# coyote_1.net
KiCad netlist of a schematic drawn in EAGLE
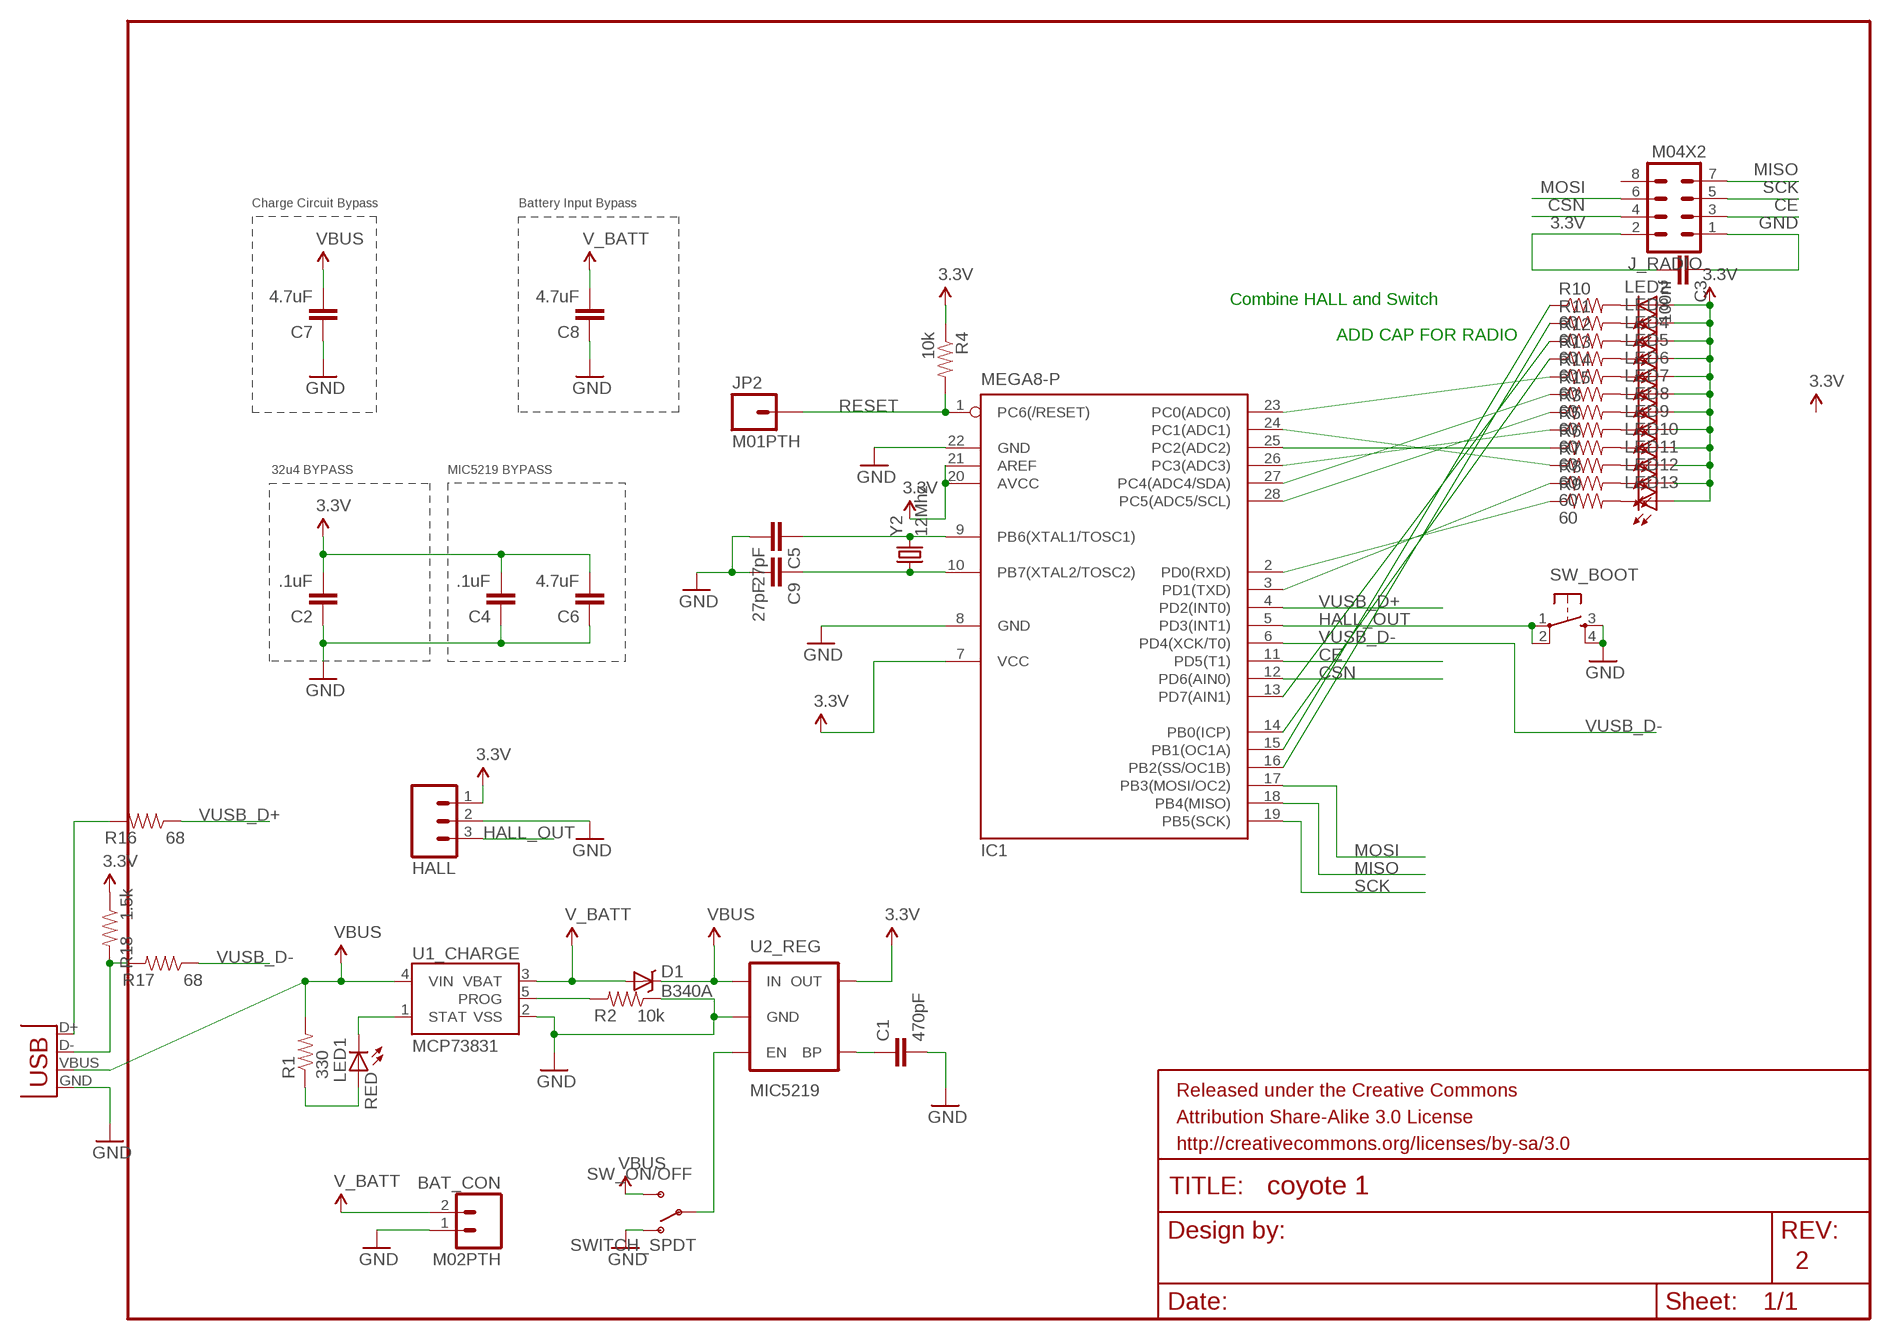
[diagram p0: schematic, sheet 1]

(export (version "E")
  (design (tool "Eeschema 10.0.6"))
  (components
    (comp (ref "BAT_CON")
      (value "M02PTH")
      (footprint "eagle-import:1X02")
      (libsource (lib "eagle-import") (part "M02PTH"))
    )
    (comp (ref "C1")
      (value "470pF")
      (footprint "eagle-import:1206")
      (libsource (lib "eagle-import") (part "CAP1206"))
    )
    (comp (ref "C2")
      (value ".1uF")
      (footprint "eagle-import:1206")
      (libsource (lib "eagle-import") (part "CAP1206"))
    )
    (comp (ref "C3")
      (value "100nf")
      (footprint "eagle-import:1206")
      (libsource (lib "eagle-import") (part "CAP1206"))
    )
    (comp (ref "C4")
      (value ".1uF")
      (footprint "eagle-import:1206")
      (libsource (lib "eagle-import") (part "CAP1206"))
    )
    (comp (ref "C5")
      (value "27pF")
      (footprint "eagle-import:1206")
      (libsource (lib "eagle-import") (part "CAP1206"))
    )
    (comp (ref "C6")
      (value "4.7uF")
      (footprint "eagle-import:1206")
      (libsource (lib "eagle-import") (part "CAP1206"))
    )
    (comp (ref "C7")
      (value "4.7uF")
      (footprint "eagle-import:1206")
      (libsource (lib "eagle-import") (part "CAP1206"))
    )
    (comp (ref "C8")
      (value "4.7uF")
      (footprint "eagle-import:1206")
      (libsource (lib "eagle-import") (part "CAP1206"))
    )
    (comp (ref "C9")
      (value "27pF")
      (footprint "eagle-import:1206")
      (libsource (lib "eagle-import") (part "CAP1206"))
    )
    (comp (ref "D1")
      (value "B340A")
      (footprint "eagle-import:SMA-DIODE")
      (libsource (lib "eagle-import") (part "DIODE-SCHOTTKY_"))
    )
    (comp (ref "HALL")
      (value "M03PTH")
      (footprint "eagle-import:1X03")
      (libsource (lib "eagle-import") (part "M03PTH"))
    )
    (comp (ref "IC1")
      (value "MEGA8-P")
      (footprint "eagle-import:DIL28-3")
      (libsource (lib "eagle-import") (part "MEGA8-P"))
    )
    (comp (ref "JP1")
      (value "USB-MB-H")
      (footprint "eagle-import:USB-MB-H")
      (libsource (lib "eagle-import") (part "USB-MB-H"))
    )
    (comp (ref "JP2")
      (value "M01PTH")
      (footprint "eagle-import:1X01")
      (libsource (lib "eagle-import") (part "M01PTH"))
    )
    (comp (ref "J_RADIO")
      (value "M04X2")
      (footprint "eagle-import:2X4")
      (libsource (lib "eagle-import") (part "M04X2"))
    )
    (comp (ref "LED1")
      (value "RED")
      (footprint "eagle-import:LED-1206")
      (libsource (lib "eagle-import") (part "LED1206"))
    )
    (comp (ref "LED2")
      (value "LED1206")
      (footprint "eagle-import:LED-1206")
      (libsource (lib "eagle-import") (part "LED1206"))
    )
    (comp (ref "LED3")
      (value "LED1206")
      (footprint "eagle-import:LED-1206")
      (libsource (lib "eagle-import") (part "LED1206"))
    )
    (comp (ref "LED4")
      (value "LED1206")
      (footprint "eagle-import:LED-1206")
      (libsource (lib "eagle-import") (part "LED1206"))
    )
    (comp (ref "LED5")
      (value "LED1206")
      (footprint "eagle-import:LED-1206")
      (libsource (lib "eagle-import") (part "LED1206"))
    )
    (comp (ref "LED6")
      (value "LED1206")
      (footprint "eagle-import:LED-1206")
      (libsource (lib "eagle-import") (part "LED1206"))
    )
    (comp (ref "LED7")
      (value "LED1206")
      (footprint "eagle-import:LED-1206")
      (libsource (lib "eagle-import") (part "LED1206"))
    )
    (comp (ref "LED8")
      (value "LED1206")
      (footprint "eagle-import:LED-1206")
      (libsource (lib "eagle-import") (part "LED1206"))
    )
    (comp (ref "LED9")
      (value "LED1206")
      (footprint "eagle-import:LED-1206")
      (libsource (lib "eagle-import") (part "LED1206"))
    )
    (comp (ref "LED10")
      (value "LED1206")
      (footprint "eagle-import:LED-1206")
      (libsource (lib "eagle-import") (part "LED1206"))
    )
    (comp (ref "LED11")
      (value "LED1206")
      (footprint "eagle-import:LED-1206")
      (libsource (lib "eagle-import") (part "LED1206"))
    )
    (comp (ref "LED12")
      (value "LED1206")
      (footprint "eagle-import:LED-1206")
      (libsource (lib "eagle-import") (part "LED1206"))
    )
    (comp (ref "LED13")
      (value "LED1206")
      (footprint "eagle-import:LED-1206")
      (libsource (lib "eagle-import") (part "LED1206"))
    )
    (comp (ref "R1")
      (value "330")
      (footprint "eagle-import:1206")
      (libsource (lib "eagle-import") (part "RESISTOR1206"))
    )
    (comp (ref "R2")
      (value "10k")
      (footprint "eagle-import:1206")
      (libsource (lib "eagle-import") (part "RESISTOR1206"))
    )
    (comp (ref "R3")
      (value "60")
      (footprint "eagle-import:1206")
      (libsource (lib "eagle-import") (part "RESISTOR1206"))
    )
    (comp (ref "R4")
      (value "10k")
      (footprint "eagle-import:1206")
      (libsource (lib "eagle-import") (part "RESISTOR1206"))
    )
    (comp (ref "R5")
      (value "60")
      (footprint "eagle-import:1206")
      (libsource (lib "eagle-import") (part "RESISTOR1206"))
    )
    (comp (ref "R6")
      (value "60")
      (footprint "eagle-import:1206")
      (libsource (lib "eagle-import") (part "RESISTOR1206"))
    )
    (comp (ref "R7")
      (value "60")
      (footprint "eagle-import:1206")
      (libsource (lib "eagle-import") (part "RESISTOR1206"))
    )
    (comp (ref "R8")
      (value "60")
      (footprint "eagle-import:1206")
      (libsource (lib "eagle-import") (part "RESISTOR1206"))
    )
    (comp (ref "R9")
      (value "60")
      (footprint "eagle-import:1206")
      (libsource (lib "eagle-import") (part "RESISTOR1206"))
    )
    (comp (ref "R10")
      (value "60")
      (footprint "eagle-import:1206")
      (libsource (lib "eagle-import") (part "RESISTOR1206"))
    )
    (comp (ref "R11")
      (value "60")
      (footprint "eagle-import:1206")
      (libsource (lib "eagle-import") (part "RESISTOR1206"))
    )
    (comp (ref "R12")
      (value "60")
      (footprint "eagle-import:1206")
      (libsource (lib "eagle-import") (part "RESISTOR1206"))
    )
    (comp (ref "R13")
      (value "60")
      (footprint "eagle-import:1206")
      (libsource (lib "eagle-import") (part "RESISTOR1206"))
    )
    (comp (ref "R14")
      (value "60")
      (footprint "eagle-import:1206")
      (libsource (lib "eagle-import") (part "RESISTOR1206"))
    )
    (comp (ref "R15")
      (value "60")
      (footprint "eagle-import:1206")
      (libsource (lib "eagle-import") (part "RESISTOR1206"))
    )
    (comp (ref "R16")
      (value "68")
      (footprint "eagle-import:1206")
      (libsource (lib "eagle-import") (part "RESISTOR1206"))
    )
    (comp (ref "R17")
      (value "68")
      (footprint "eagle-import:1206")
      (libsource (lib "eagle-import") (part "RESISTOR1206"))
    )
    (comp (ref "R18")
      (value "1.5k")
      (footprint "eagle-import:1206")
      (libsource (lib "eagle-import") (part "RESISTOR1206"))
    )
    (comp (ref "SW_BOOT")
      (value "TAC_SWITCHPTH")
      (footprint "eagle-import:TACTILE-PTH")
      (libsource (lib "eagle-import") (part "TAC_SWITCHPTH"))
    )
    (comp (ref "SW_ON/OFF")
      (value "SWITCH_SPDT")
      (footprint "eagle-import:KPS-1290")
      (libsource (lib "eagle-import") (part "SWITCH_SPDT"))
    )
    (comp (ref "U1_CHARGE")
      (value "MCP73831")
      (footprint "eagle-import:SOT23-5")
      (libsource (lib "eagle-import") (part "MCP73831"))
    )
    (comp (ref "U2_REG")
      (value "MIC5219")
      (footprint "eagle-import:SOT23-5")
      (libsource (lib "eagle-import") (part "V_REG_MIC5219SMD"))
    )
    (comp (ref "Y2")
      (value "12Mhz")
      (footprint "eagle-import:HC49US")
      (libsource (lib "eagle-import") (part "CRYSTALHC49US"))
    )
  )
  (nets
    (net (code "1") (name "/CE") (class "Default")
      (node (ref "IC1") (pin "11") (pinfunction "PD5(T1)_11") (pintype "bidirectional"))
      (node (ref "J_RADIO") (pin "3") (pinfunction "3_3") (pintype "passive"))
    )
    (net (code "2") (name "/CSN") (class "Default")
      (node (ref "IC1") (pin "12") (pinfunction "PD6(AIN0)_12") (pintype "bidirectional"))
      (node (ref "J_RADIO") (pin "4") (pinfunction "4_4") (pintype "passive"))
    )
    (net (code "3") (name "/HALL_OUT") (class "Default")
      (node (ref "HALL") (pin "3") (pinfunction "3_3") (pintype "passive"))
      (node (ref "IC1") (pin "5") (pinfunction "PD3(INT1)_5") (pintype "bidirectional"))
      (node (ref "SW_BOOT") (pin "1") (pinfunction "1_1") (pintype "passive"))
      (node (ref "SW_BOOT") (pin "2") (pinfunction "2_2") (pintype "passive"))
    )
    (net (code "4") (name "/MISO") (class "Default")
      (node (ref "IC1") (pin "18") (pinfunction "PB4(MISO)_18") (pintype "bidirectional"))
      (node (ref "J_RADIO") (pin "7") (pinfunction "7_7") (pintype "passive"))
    )
    (net (code "5") (name "/MOSI") (class "Default")
      (node (ref "IC1") (pin "17") (pinfunction "PB3(MOSI/OC2)_17") (pintype "bidirectional"))
      (node (ref "J_RADIO") (pin "6") (pinfunction "6_6") (pintype "passive"))
    )
    (net (code "6") (name "/RESET") (class "Default")
      (node (ref "IC1") (pin "1") (pinfunction "PC6(/RESET)_1") (pintype "bidirectional"))
      (node (ref "JP2") (pin "1") (pinfunction "1_1") (pintype "passive"))
      (node (ref "R4") (pin "2") (pinfunction "2_2") (pintype "passive"))
    )
    (net (code "7") (name "/SCK") (class "Default")
      (node (ref "IC1") (pin "19") (pinfunction "PB5(SCK)_19") (pintype "bidirectional"))
      (node (ref "J_RADIO") (pin "5") (pinfunction "5_5") (pintype "passive"))
    )
    (net (code "8") (name "/VUSB_D+") (class "Default")
      (node (ref "IC1") (pin "4") (pinfunction "PD2(INT0)_4") (pintype "bidirectional"))
      (node (ref "R16") (pin "1") (pinfunction "1_1") (pintype "passive"))
    )
    (net (code "9") (name "/VUSB_D-") (class "Default")
      (node (ref "IC1") (pin "6") (pinfunction "PD4(XCK/T0)_6") (pintype "bidirectional"))
      (node (ref "R17") (pin "1") (pinfunction "1_1") (pintype "passive"))
    )
    (net (code "10") (name "3.3V") (class "Default")
      (node (ref "C2") (pin "2") (pinfunction "2_2") (pintype "passive"))
      (node (ref "C3") (pin "2") (pinfunction "2_2") (pintype "passive"))
      (node (ref "C4") (pin "2") (pinfunction "2_2") (pintype "passive"))
      (node (ref "C6") (pin "2") (pinfunction "2_2") (pintype "passive"))
      (node (ref "HALL") (pin "1") (pinfunction "1_1") (pintype "passive"))
      (node (ref "IC1") (pin "20") (pinfunction "AVCC_20") (pintype "power_in"))
      (node (ref "IC1") (pin "21") (pinfunction "AREF_21") (pintype "passive"))
      (node (ref "IC1") (pin "7") (pinfunction "VCC_7") (pintype "power_in"))
      (node (ref "J_RADIO") (pin "2") (pinfunction "2_2") (pintype "passive"))
      (node (ref "LED10") (pin "A") (pinfunction "A_A") (pintype "passive"))
      (node (ref "LED11") (pin "A") (pinfunction "A_A") (pintype "passive"))
      (node (ref "LED12") (pin "A") (pinfunction "A_A") (pintype "passive"))
      (node (ref "LED13") (pin "A") (pinfunction "A_A") (pintype "passive"))
      (node (ref "LED2") (pin "A") (pinfunction "A_A") (pintype "passive"))
      (node (ref "LED3") (pin "A") (pinfunction "A_A") (pintype "passive"))
      (node (ref "LED4") (pin "A") (pinfunction "A_A") (pintype "passive"))
      (node (ref "LED5") (pin "A") (pinfunction "A_A") (pintype "passive"))
      (node (ref "LED6") (pin "A") (pinfunction "A_A") (pintype "passive"))
      (node (ref "LED7") (pin "A") (pinfunction "A_A") (pintype "passive"))
      (node (ref "LED8") (pin "A") (pinfunction "A_A") (pintype "passive"))
      (node (ref "LED9") (pin "A") (pinfunction "A_A") (pintype "passive"))
      (node (ref "R18") (pin "1") (pinfunction "1_1") (pintype "passive"))
      (node (ref "R4") (pin "1") (pinfunction "1_1") (pintype "passive"))
      (node (ref "U2_REG") (pin "5") (pinfunction "OUT_5") (pintype "passive"))
    )
    (net (code "11") (name "GND") (class "Default")
      (node (ref "BAT_CON") (pin "1") (pinfunction "1_1") (pintype "passive"))
      (node (ref "C1") (pin "2") (pinfunction "2_2") (pintype "passive"))
      (node (ref "C2") (pin "1") (pinfunction "1_1") (pintype "passive"))
      (node (ref "C3") (pin "1") (pinfunction "1_1") (pintype "passive"))
      (node (ref "C4") (pin "1") (pinfunction "1_1") (pintype "passive"))
      (node (ref "C5") (pin "2") (pinfunction "2_2") (pintype "passive"))
      (node (ref "C6") (pin "1") (pinfunction "1_1") (pintype "passive"))
      (node (ref "C7") (pin "1") (pinfunction "1_1") (pintype "passive"))
      (node (ref "C8") (pin "1") (pinfunction "1_1") (pintype "passive"))
      (node (ref "C9") (pin "2") (pinfunction "2_2") (pintype "passive"))
      (node (ref "HALL") (pin "2") (pinfunction "2_2") (pintype "passive"))
      (node (ref "IC1") (pin "22") (pinfunction "GND_22") (pintype "power_in"))
      (node (ref "IC1") (pin "8") (pinfunction "GND_8") (pintype "power_in"))
      (node (ref "JP1") (pin "GND") (pinfunction "GND_GND") (pintype "bidirectional"))
      (node (ref "J_RADIO") (pin "1") (pinfunction "1_1") (pintype "passive"))
      (node (ref "R2") (pin "1") (pinfunction "1_1") (pintype "passive"))
      (node (ref "SW_BOOT") (pin "3") (pinfunction "3_3") (pintype "passive"))
      (node (ref "SW_BOOT") (pin "4") (pinfunction "4_4") (pintype "passive"))
      (node (ref "SW_ON/OFF") (pin "O") (pinfunction "O_O") (pintype "passive"))
      (node (ref "U1_CHARGE") (pin "2") (pinfunction "VSS_2") (pintype "power_in"))
      (node (ref "U2_REG") (pin "2") (pinfunction "GND_2") (pintype "input"))
    )
    (net (code "12") (name "Net-(IC1-PB0(ICP))") (class "Default")
      (node (ref "IC1") (pin "14") (pinfunction "PB0(ICP)_14") (pintype "bidirectional"))
      (node (ref "R13") (pin "1") (pinfunction "1_1") (pintype "passive"))
    )
    (net (code "13") (name "Net-(IC1-PB1(OC1A))") (class "Default")
      (node (ref "IC1") (pin "15") (pinfunction "PB1(OC1A)_15") (pintype "bidirectional"))
      (node (ref "R10") (pin "1") (pinfunction "1_1") (pintype "passive"))
    )
    (net (code "14") (name "Net-(IC1-PB2(SS{slash}OC1B))") (class "Default")
      (node (ref "IC1") (pin "16") (pinfunction "PB2(SS/OC1B)_16") (pintype "bidirectional"))
      (node (ref "R11") (pin "1") (pinfunction "1_1") (pintype "passive"))
    )
    (net (code "15") (name "Net-(IC1-PB6(XTAL1{slash}TOSC1))") (class "Default")
      (node (ref "C5") (pin "1") (pinfunction "1_1") (pintype "passive"))
      (node (ref "IC1") (pin "9") (pinfunction "PB6(XTAL1/TOSC1)_9") (pintype "bidirectional"))
      (node (ref "Y2") (pin "2") (pinfunction "2_2") (pintype "passive"))
    )
    (net (code "16") (name "Net-(IC1-PB7(XTAL2{slash}TOSC2))") (class "Default")
      (node (ref "C9") (pin "1") (pinfunction "1_1") (pintype "passive"))
      (node (ref "IC1") (pin "10") (pinfunction "PB7(XTAL2/TOSC2)_10") (pintype "bidirectional"))
      (node (ref "Y2") (pin "1") (pinfunction "1_1") (pintype "passive"))
    )
    (net (code "17") (name "Net-(IC1-PC0(ADC0))") (class "Default")
      (node (ref "IC1") (pin "23") (pinfunction "PC0(ADC0)_23") (pintype "bidirectional"))
      (node (ref "R14") (pin "1") (pinfunction "1_1") (pintype "passive"))
    )
    (net (code "18") (name "Net-(IC1-PC1(ADC1))") (class "Default")
      (node (ref "IC1") (pin "24") (pinfunction "PC1(ADC1)_24") (pintype "bidirectional"))
      (node (ref "R7") (pin "1") (pinfunction "1_1") (pintype "passive"))
    )
    (net (code "19") (name "Net-(IC1-PC2(ADC2))") (class "Default")
      (node (ref "IC1") (pin "25") (pinfunction "PC2(ADC2)_25") (pintype "bidirectional"))
      (node (ref "R6") (pin "1") (pinfunction "1_1") (pintype "passive"))
    )
    (net (code "20") (name "Net-(IC1-PC3(ADC3))") (class "Default")
      (node (ref "IC1") (pin "26") (pinfunction "PC3(ADC3)_26") (pintype "bidirectional"))
      (node (ref "R5") (pin "1") (pinfunction "1_1") (pintype "passive"))
    )
    (net (code "21") (name "Net-(IC1-PC4(ADC4{slash}SDA))") (class "Default")
      (node (ref "IC1") (pin "27") (pinfunction "PC4(ADC4/SDA)_27") (pintype "bidirectional"))
      (node (ref "R15") (pin "1") (pinfunction "1_1") (pintype "passive"))
    )
    (net (code "22") (name "Net-(IC1-PC5(ADC5{slash}SCL))") (class "Default")
      (node (ref "IC1") (pin "28") (pinfunction "PC5(ADC5/SCL)_28") (pintype "bidirectional"))
      (node (ref "R3") (pin "1") (pinfunction "1_1") (pintype "passive"))
    )
    (net (code "23") (name "Net-(IC1-PD0(RXD))") (class "Default")
      (node (ref "IC1") (pin "2") (pinfunction "PD0(RXD)_2") (pintype "bidirectional"))
      (node (ref "R9") (pin "1") (pinfunction "1_1") (pintype "passive"))
    )
    (net (code "24") (name "Net-(IC1-PD1(TXD))") (class "Default")
      (node (ref "IC1") (pin "3") (pinfunction "PD1(TXD)_3") (pintype "bidirectional"))
      (node (ref "R8") (pin "1") (pinfunction "1_1") (pintype "passive"))
    )
    (net (code "25") (name "Net-(IC1-PD7(AIN1))") (class "Default")
      (node (ref "IC1") (pin "13") (pinfunction "PD7(AIN1)_13") (pintype "bidirectional"))
      (node (ref "R12") (pin "1") (pinfunction "1_1") (pintype "passive"))
    )
    (net (code "26") (name "Net-(JP1-PadD+)") (class "Default")
      (node (ref "JP1") (pin "D+") (pinfunction "D+_D+") (pintype "bidirectional"))
      (node (ref "R16") (pin "2") (pinfunction "2_2") (pintype "passive"))
    )
    (net (code "27") (name "Net-(JP1-PadD-)") (class "Default")
      (node (ref "JP1") (pin "D-") (pinfunction "D-_D-") (pintype "bidirectional"))
      (node (ref "R17") (pin "2") (pinfunction "2_2") (pintype "passive"))
      (node (ref "R18") (pin "2") (pinfunction "2_2") (pintype "passive"))
    )
    (net (code "28") (name "Net-(LED1-PadA)") (class "Default")
      (node (ref "LED1") (pin "A") (pinfunction "A_A") (pintype "passive"))
      (node (ref "R1") (pin "1") (pinfunction "1_1") (pintype "passive"))
    )
    (net (code "29") (name "Net-(LED2-PadC)") (class "Default")
      (node (ref "LED2") (pin "C") (pinfunction "C_C") (pintype "passive"))
      (node (ref "R10") (pin "2") (pinfunction "2_2") (pintype "passive"))
    )
    (net (code "30") (name "Net-(LED3-PadC)") (class "Default")
      (node (ref "LED3") (pin "C") (pinfunction "C_C") (pintype "passive"))
      (node (ref "R11") (pin "2") (pinfunction "2_2") (pintype "passive"))
    )
    (net (code "31") (name "Net-(LED4-PadC)") (class "Default")
      (node (ref "LED4") (pin "C") (pinfunction "C_C") (pintype "passive"))
      (node (ref "R12") (pin "2") (pinfunction "2_2") (pintype "passive"))
    )
    (net (code "32") (name "Net-(LED5-PadC)") (class "Default")
      (node (ref "LED5") (pin "C") (pinfunction "C_C") (pintype "passive"))
      (node (ref "R13") (pin "2") (pinfunction "2_2") (pintype "passive"))
    )
    (net (code "33") (name "Net-(LED6-PadC)") (class "Default")
      (node (ref "LED6") (pin "C") (pinfunction "C_C") (pintype "passive"))
      (node (ref "R14") (pin "2") (pinfunction "2_2") (pintype "passive"))
    )
    (net (code "34") (name "Net-(LED7-PadC)") (class "Default")
      (node (ref "LED7") (pin "C") (pinfunction "C_C") (pintype "passive"))
      (node (ref "R15") (pin "2") (pinfunction "2_2") (pintype "passive"))
    )
    (net (code "35") (name "Net-(LED8-PadC)") (class "Default")
      (node (ref "LED8") (pin "C") (pinfunction "C_C") (pintype "passive"))
      (node (ref "R3") (pin "2") (pinfunction "2_2") (pintype "passive"))
    )
    (net (code "36") (name "Net-(LED9-PadC)") (class "Default")
      (node (ref "LED9") (pin "C") (pinfunction "C_C") (pintype "passive"))
      (node (ref "R5") (pin "2") (pinfunction "2_2") (pintype "passive"))
    )
    (net (code "37") (name "Net-(LED10-PadC)") (class "Default")
      (node (ref "LED10") (pin "C") (pinfunction "C_C") (pintype "passive"))
      (node (ref "R6") (pin "2") (pinfunction "2_2") (pintype "passive"))
    )
    (net (code "38") (name "Net-(LED11-PadC)") (class "Default")
      (node (ref "LED11") (pin "C") (pinfunction "C_C") (pintype "passive"))
      (node (ref "R7") (pin "2") (pinfunction "2_2") (pintype "passive"))
    )
    (net (code "39") (name "Net-(LED12-PadC)") (class "Default")
      (node (ref "LED12") (pin "C") (pinfunction "C_C") (pintype "passive"))
      (node (ref "R8") (pin "2") (pinfunction "2_2") (pintype "passive"))
    )
    (net (code "40") (name "Net-(LED13-PadC)") (class "Default")
      (node (ref "LED13") (pin "C") (pinfunction "C_C") (pintype "passive"))
      (node (ref "R9") (pin "2") (pinfunction "2_2") (pintype "passive"))
    )
    (net (code "41") (name "Net-(U1_CHARGE-PROG)") (class "Default")
      (node (ref "R2") (pin "2") (pinfunction "2_2") (pintype "passive"))
      (node (ref "U1_CHARGE") (pin "5") (pinfunction "PROG_5") (pintype "input"))
    )
    (net (code "42") (name "Net-(U1_CHARGE-STAT)") (class "Default")
      (node (ref "LED1") (pin "C") (pinfunction "C_C") (pintype "passive"))
      (node (ref "U1_CHARGE") (pin "1") (pinfunction "STAT_1") (pintype "output"))
    )
    (net (code "43") (name "Net-(U2_REG-BP)") (class "Default")
      (node (ref "C1") (pin "1") (pinfunction "1_1") (pintype "passive"))
      (node (ref "U2_REG") (pin "4") (pinfunction "BP_4") (pintype "input"))
    )
    (net (code "44") (name "Net-(U2_REG-EN)") (class "Default")
      (node (ref "SW_ON/OFF") (pin "P") (pinfunction "P_P") (pintype "passive"))
      (node (ref "U2_REG") (pin "3") (pinfunction "EN_3") (pintype "input"))
    )
    (net (code "45") (name "VBUS") (class "Default")
      (node (ref "C7") (pin "2") (pinfunction "2_2") (pintype "passive"))
      (node (ref "D1") (pin "C") (pinfunction "C_C") (pintype "passive"))
      (node (ref "JP1") (pin "VBUS") (pinfunction "VBUS_VBUS") (pintype "bidirectional"))
      (node (ref "R1") (pin "2") (pinfunction "2_2") (pintype "passive"))
      (node (ref "SW_ON/OFF") (pin "S") (pinfunction "S_S") (pintype "passive"))
      (node (ref "U1_CHARGE") (pin "4") (pinfunction "VIN_4") (pintype "power_in"))
      (node (ref "U2_REG") (pin "1") (pinfunction "IN_1") (pintype "input"))
    )
    (net (code "46") (name "V_BATT") (class "Default")
      (node (ref "BAT_CON") (pin "2") (pinfunction "2_2") (pintype "passive"))
      (node (ref "C8") (pin "2") (pinfunction "2_2") (pintype "passive"))
      (node (ref "D1") (pin "A") (pinfunction "A_A") (pintype "passive"))
      (node (ref "U1_CHARGE") (pin "3") (pinfunction "VBAT_3") (pintype "power_in"))
    )
    (net (code "47") (name "unconnected-(J_RADIO-Pad8)") (class "Default")
      (node (ref "J_RADIO") (pin "8") (pinfunction "8_8") (pintype "passive"))
    )
  )
)
